# ognite.net
KiCad netlist of a schematic drawn in EAGLE
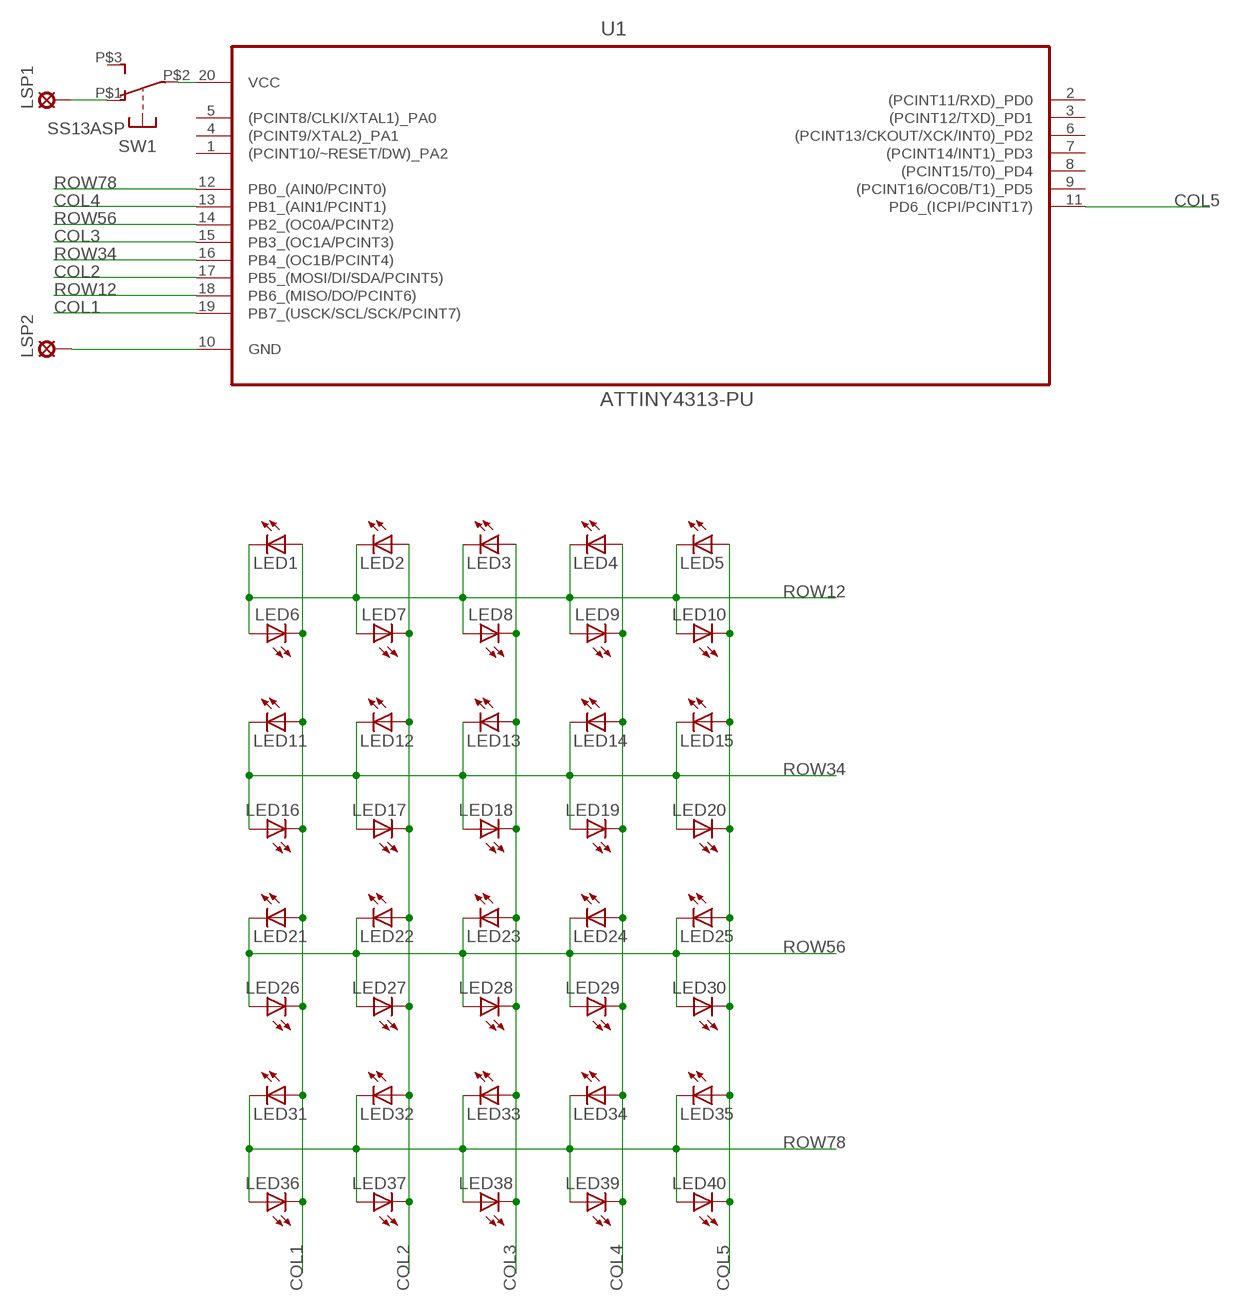
[diagram p0: schematic, sheet 1]

(export (version "E")
  (design (tool "Eeschema 10.0.6"))
  (components
    (comp (ref "LED1")
      (value "LED3MM")
      (footprint "eagle-import:LED3MM")
      (libsource (lib "eagle-import") (part "LED3MM"))
    )
    (comp (ref "LED2")
      (value "LED3MM")
      (footprint "eagle-import:LED3MM")
      (libsource (lib "eagle-import") (part "LED3MM"))
    )
    (comp (ref "LED3")
      (value "LED3MM")
      (footprint "eagle-import:LED3MM")
      (libsource (lib "eagle-import") (part "LED3MM"))
    )
    (comp (ref "LED4")
      (value "LED3MM")
      (footprint "eagle-import:LED3MM")
      (libsource (lib "eagle-import") (part "LED3MM"))
    )
    (comp (ref "LED5")
      (value "LED3MM")
      (footprint "eagle-import:LED3MM")
      (libsource (lib "eagle-import") (part "LED3MM"))
    )
    (comp (ref "LED6")
      (value "LED3MM")
      (footprint "eagle-import:LED3MM")
      (libsource (lib "eagle-import") (part "LED3MM"))
    )
    (comp (ref "LED7")
      (value "LED3MM")
      (footprint "eagle-import:LED3MM")
      (libsource (lib "eagle-import") (part "LED3MM"))
    )
    (comp (ref "LED8")
      (value "LED3MM")
      (footprint "eagle-import:LED3MM")
      (libsource (lib "eagle-import") (part "LED3MM"))
    )
    (comp (ref "LED9")
      (value "LED3MM")
      (footprint "eagle-import:LED3MM")
      (libsource (lib "eagle-import") (part "LED3MM"))
    )
    (comp (ref "LED10")
      (value "LED3MM")
      (footprint "eagle-import:LED3MM")
      (libsource (lib "eagle-import") (part "LED3MM"))
    )
    (comp (ref "LED11")
      (value "LED3MM")
      (footprint "eagle-import:LED3MM")
      (libsource (lib "eagle-import") (part "LED3MM"))
    )
    (comp (ref "LED12")
      (value "LED3MM")
      (footprint "eagle-import:LED3MM")
      (libsource (lib "eagle-import") (part "LED3MM"))
    )
    (comp (ref "LED13")
      (value "LED3MM")
      (footprint "eagle-import:LED3MM")
      (libsource (lib "eagle-import") (part "LED3MM"))
    )
    (comp (ref "LED14")
      (value "LED3MM")
      (footprint "eagle-import:LED3MM")
      (libsource (lib "eagle-import") (part "LED3MM"))
    )
    (comp (ref "LED15")
      (value "LED3MM")
      (footprint "eagle-import:LED3MM")
      (libsource (lib "eagle-import") (part "LED3MM"))
    )
    (comp (ref "LED16")
      (value "LED3MM")
      (footprint "eagle-import:LED3MM")
      (libsource (lib "eagle-import") (part "LED3MM"))
    )
    (comp (ref "LED17")
      (value "LED3MM")
      (footprint "eagle-import:LED3MM")
      (libsource (lib "eagle-import") (part "LED3MM"))
    )
    (comp (ref "LED18")
      (value "LED3MM")
      (footprint "eagle-import:LED3MM")
      (libsource (lib "eagle-import") (part "LED3MM"))
    )
    (comp (ref "LED19")
      (value "LED3MM")
      (footprint "eagle-import:LED3MM")
      (libsource (lib "eagle-import") (part "LED3MM"))
    )
    (comp (ref "LED20")
      (value "LED3MM")
      (footprint "eagle-import:LED3MM")
      (libsource (lib "eagle-import") (part "LED3MM"))
    )
    (comp (ref "LED21")
      (value "LED3MM")
      (footprint "eagle-import:LED3MM")
      (libsource (lib "eagle-import") (part "LED3MM"))
    )
    (comp (ref "LED22")
      (value "LED3MM")
      (footprint "eagle-import:LED3MM")
      (libsource (lib "eagle-import") (part "LED3MM"))
    )
    (comp (ref "LED23")
      (value "LED3MM")
      (footprint "eagle-import:LED3MM")
      (libsource (lib "eagle-import") (part "LED3MM"))
    )
    (comp (ref "LED24")
      (value "LED3MM")
      (footprint "eagle-import:LED3MM")
      (libsource (lib "eagle-import") (part "LED3MM"))
    )
    (comp (ref "LED25")
      (value "LED3MM")
      (footprint "eagle-import:LED3MM")
      (libsource (lib "eagle-import") (part "LED3MM"))
    )
    (comp (ref "LED26")
      (value "LED3MM")
      (footprint "eagle-import:LED3MM")
      (libsource (lib "eagle-import") (part "LED3MM"))
    )
    (comp (ref "LED27")
      (value "LED3MM")
      (footprint "eagle-import:LED3MM")
      (libsource (lib "eagle-import") (part "LED3MM"))
    )
    (comp (ref "LED28")
      (value "LED3MM")
      (footprint "eagle-import:LED3MM")
      (libsource (lib "eagle-import") (part "LED3MM"))
    )
    (comp (ref "LED29")
      (value "LED3MM")
      (footprint "eagle-import:LED3MM")
      (libsource (lib "eagle-import") (part "LED3MM"))
    )
    (comp (ref "LED30")
      (value "LED3MM")
      (footprint "eagle-import:LED3MM")
      (libsource (lib "eagle-import") (part "LED3MM"))
    )
    (comp (ref "LED31")
      (value "LED3MM")
      (footprint "eagle-import:LED3MM")
      (libsource (lib "eagle-import") (part "LED3MM"))
    )
    (comp (ref "LED32")
      (value "LED3MM")
      (footprint "eagle-import:LED3MM")
      (libsource (lib "eagle-import") (part "LED3MM"))
    )
    (comp (ref "LED33")
      (value "LED3MM")
      (footprint "eagle-import:LED3MM")
      (libsource (lib "eagle-import") (part "LED3MM"))
    )
    (comp (ref "LED34")
      (value "LED3MM")
      (footprint "eagle-import:LED3MM")
      (libsource (lib "eagle-import") (part "LED3MM"))
    )
    (comp (ref "LED35")
      (value "LED3MM")
      (footprint "eagle-import:LED3MM")
      (libsource (lib "eagle-import") (part "LED3MM"))
    )
    (comp (ref "LED36")
      (value "LED3MM")
      (footprint "eagle-import:LED3MM")
      (libsource (lib "eagle-import") (part "LED3MM"))
    )
    (comp (ref "LED37")
      (value "LED3MM")
      (footprint "eagle-import:LED3MM")
      (libsource (lib "eagle-import") (part "LED3MM"))
    )
    (comp (ref "LED38")
      (value "LED3MM")
      (footprint "eagle-import:LED3MM")
      (libsource (lib "eagle-import") (part "LED3MM"))
    )
    (comp (ref "LED39")
      (value "LED3MM")
      (footprint "eagle-import:LED3MM")
      (libsource (lib "eagle-import") (part "LED3MM"))
    )
    (comp (ref "LED40")
      (value "LED3MM")
      (footprint "eagle-import:LED3MM")
      (libsource (lib "eagle-import") (part "LED3MM"))
    )
    (comp (ref "LSP1")
      (value "SE14")
      (footprint "eagle-import:SE14")
      (libsource (lib "eagle-import") (part "SE14"))
    )
    (comp (ref "LSP2")
      (value "SE14")
      (footprint "eagle-import:SE14")
      (libsource (lib "eagle-import") (part "SE14"))
    )
    (comp (ref "SW1")
      (value "SS13ASP")
      (footprint "eagle-import:T80-S")
      (libsource (lib "eagle-import") (part "SS13ASP"))
    )
    (comp (ref "U1")
      (value "ATTINY4313-PU")
      (footprint "eagle-import:DIP254P762X533-20")
      (libsource (lib "eagle-import") (part "ATTINY4313-PU"))
    )
  )
  (nets
    (net (code "1") (name "/COL1") (class "Default")
      (node (ref "LED1") (pin "A") (pinfunction "A_A") (pintype "passive"))
      (node (ref "LED11") (pin "A") (pinfunction "A_A") (pintype "passive"))
      (node (ref "LED16") (pin "K") (pinfunction "C_K") (pintype "passive"))
      (node (ref "LED21") (pin "A") (pinfunction "A_A") (pintype "passive"))
      (node (ref "LED26") (pin "K") (pinfunction "C_K") (pintype "passive"))
      (node (ref "LED31") (pin "A") (pinfunction "A_A") (pintype "passive"))
      (node (ref "LED36") (pin "K") (pinfunction "C_K") (pintype "passive"))
      (node (ref "LED6") (pin "K") (pinfunction "C_K") (pintype "passive"))
      (node (ref "U1") (pin "19") (pinfunction "PB7_(USCK/SCL/SCK/PCINT7)_19") (pintype "bidirectional"))
    )
    (net (code "2") (name "/COL2") (class "Default")
      (node (ref "LED12") (pin "A") (pinfunction "A_A") (pintype "passive"))
      (node (ref "LED17") (pin "K") (pinfunction "C_K") (pintype "passive"))
      (node (ref "LED2") (pin "A") (pinfunction "A_A") (pintype "passive"))
      (node (ref "LED22") (pin "A") (pinfunction "A_A") (pintype "passive"))
      (node (ref "LED27") (pin "K") (pinfunction "C_K") (pintype "passive"))
      (node (ref "LED32") (pin "A") (pinfunction "A_A") (pintype "passive"))
      (node (ref "LED37") (pin "K") (pinfunction "C_K") (pintype "passive"))
      (node (ref "LED7") (pin "K") (pinfunction "C_K") (pintype "passive"))
      (node (ref "U1") (pin "17") (pinfunction "PB5_(MOSI/DI/SDA/PCINT5)_17") (pintype "bidirectional"))
    )
    (net (code "3") (name "/COL3") (class "Default")
      (node (ref "LED13") (pin "A") (pinfunction "A_A") (pintype "passive"))
      (node (ref "LED18") (pin "K") (pinfunction "C_K") (pintype "passive"))
      (node (ref "LED23") (pin "A") (pinfunction "A_A") (pintype "passive"))
      (node (ref "LED28") (pin "K") (pinfunction "C_K") (pintype "passive"))
      (node (ref "LED3") (pin "A") (pinfunction "A_A") (pintype "passive"))
      (node (ref "LED33") (pin "A") (pinfunction "A_A") (pintype "passive"))
      (node (ref "LED38") (pin "K") (pinfunction "C_K") (pintype "passive"))
      (node (ref "LED8") (pin "K") (pinfunction "C_K") (pintype "passive"))
      (node (ref "U1") (pin "15") (pinfunction "PB3_(OC1A/PCINT3)_15") (pintype "power_in"))
    )
    (net (code "4") (name "/COL4") (class "Default")
      (node (ref "LED14") (pin "A") (pinfunction "A_A") (pintype "passive"))
      (node (ref "LED19") (pin "K") (pinfunction "C_K") (pintype "passive"))
      (node (ref "LED24") (pin "A") (pinfunction "A_A") (pintype "passive"))
      (node (ref "LED29") (pin "K") (pinfunction "C_K") (pintype "passive"))
      (node (ref "LED34") (pin "A") (pinfunction "A_A") (pintype "passive"))
      (node (ref "LED39") (pin "K") (pinfunction "C_K") (pintype "passive"))
      (node (ref "LED4") (pin "A") (pinfunction "A_A") (pintype "passive"))
      (node (ref "LED9") (pin "K") (pinfunction "C_K") (pintype "passive"))
      (node (ref "U1") (pin "13") (pinfunction "PB1_(AIN1/PCINT1)_13") (pintype "bidirectional"))
    )
    (net (code "5") (name "/COL5") (class "Default")
      (node (ref "LED10") (pin "K") (pinfunction "C_K") (pintype "passive"))
      (node (ref "LED15") (pin "A") (pinfunction "A_A") (pintype "passive"))
      (node (ref "LED20") (pin "K") (pinfunction "C_K") (pintype "passive"))
      (node (ref "LED25") (pin "A") (pinfunction "A_A") (pintype "passive"))
      (node (ref "LED30") (pin "K") (pinfunction "C_K") (pintype "passive"))
      (node (ref "LED35") (pin "A") (pinfunction "A_A") (pintype "passive"))
      (node (ref "LED40") (pin "K") (pinfunction "C_K") (pintype "passive"))
      (node (ref "LED5") (pin "A") (pinfunction "A_A") (pintype "passive"))
      (node (ref "U1") (pin "11") (pinfunction "PD6_(ICPI/PCINT17)_11") (pintype "bidirectional"))
    )
    (net (code "6") (name "/ROW12") (class "Default")
      (node (ref "LED1") (pin "K") (pinfunction "C_K") (pintype "passive"))
      (node (ref "LED10") (pin "A") (pinfunction "A_A") (pintype "passive"))
      (node (ref "LED2") (pin "K") (pinfunction "C_K") (pintype "passive"))
      (node (ref "LED3") (pin "K") (pinfunction "C_K") (pintype "passive"))
      (node (ref "LED4") (pin "K") (pinfunction "C_K") (pintype "passive"))
      (node (ref "LED5") (pin "K") (pinfunction "C_K") (pintype "passive"))
      (node (ref "LED6") (pin "A") (pinfunction "A_A") (pintype "passive"))
      (node (ref "LED7") (pin "A") (pinfunction "A_A") (pintype "passive"))
      (node (ref "LED8") (pin "A") (pinfunction "A_A") (pintype "passive"))
      (node (ref "LED9") (pin "A") (pinfunction "A_A") (pintype "passive"))
      (node (ref "U1") (pin "18") (pinfunction "PB6_(MISO/DO/PCINT6)_18") (pintype "bidirectional"))
    )
    (net (code "7") (name "/ROW34") (class "Default")
      (node (ref "LED11") (pin "K") (pinfunction "C_K") (pintype "passive"))
      (node (ref "LED12") (pin "K") (pinfunction "C_K") (pintype "passive"))
      (node (ref "LED13") (pin "K") (pinfunction "C_K") (pintype "passive"))
      (node (ref "LED14") (pin "K") (pinfunction "C_K") (pintype "passive"))
      (node (ref "LED15") (pin "K") (pinfunction "C_K") (pintype "passive"))
      (node (ref "LED16") (pin "A") (pinfunction "A_A") (pintype "passive"))
      (node (ref "LED17") (pin "A") (pinfunction "A_A") (pintype "passive"))
      (node (ref "LED18") (pin "A") (pinfunction "A_A") (pintype "passive"))
      (node (ref "LED19") (pin "A") (pinfunction "A_A") (pintype "passive"))
      (node (ref "LED20") (pin "A") (pinfunction "A_A") (pintype "passive"))
      (node (ref "U1") (pin "16") (pinfunction "PB4_(OC1B/PCINT4)_16") (pintype "passive"))
    )
    (net (code "8") (name "/ROW56") (class "Default")
      (node (ref "LED21") (pin "K") (pinfunction "C_K") (pintype "passive"))
      (node (ref "LED22") (pin "K") (pinfunction "C_K") (pintype "passive"))
      (node (ref "LED23") (pin "K") (pinfunction "C_K") (pintype "passive"))
      (node (ref "LED24") (pin "K") (pinfunction "C_K") (pintype "passive"))
      (node (ref "LED25") (pin "K") (pinfunction "C_K") (pintype "passive"))
      (node (ref "LED26") (pin "A") (pinfunction "A_A") (pintype "passive"))
      (node (ref "LED27") (pin "A") (pinfunction "A_A") (pintype "passive"))
      (node (ref "LED28") (pin "A") (pinfunction "A_A") (pintype "passive"))
      (node (ref "LED29") (pin "A") (pinfunction "A_A") (pintype "passive"))
      (node (ref "LED30") (pin "A") (pinfunction "A_A") (pintype "passive"))
      (node (ref "U1") (pin "14") (pinfunction "PB2_(OC0A/PCINT2)_14") (pintype "bidirectional"))
    )
    (net (code "9") (name "/ROW78") (class "Default")
      (node (ref "LED31") (pin "K") (pinfunction "C_K") (pintype "passive"))
      (node (ref "LED32") (pin "K") (pinfunction "C_K") (pintype "passive"))
      (node (ref "LED33") (pin "K") (pinfunction "C_K") (pintype "passive"))
      (node (ref "LED34") (pin "K") (pinfunction "C_K") (pintype "passive"))
      (node (ref "LED35") (pin "K") (pinfunction "C_K") (pintype "passive"))
      (node (ref "LED36") (pin "A") (pinfunction "A_A") (pintype "passive"))
      (node (ref "LED37") (pin "A") (pinfunction "A_A") (pintype "passive"))
      (node (ref "LED38") (pin "A") (pinfunction "A_A") (pintype "passive"))
      (node (ref "LED39") (pin "A") (pinfunction "A_A") (pintype "passive"))
      (node (ref "LED40") (pin "A") (pinfunction "A_A") (pintype "passive"))
      (node (ref "U1") (pin "12") (pinfunction "PB0_(AIN0/PCINT0)_12") (pintype "bidirectional"))
    )
    (net (code "10") (name "Net-(SW1-COM)") (class "Default")
      (node (ref "SW1") (pin "P$2") (pinfunction "COM_P$2") (pintype "passive"))
      (node (ref "U1") (pin "20") (pinfunction "VCC_20") (pintype "power_in"))
    )
    (net (code "11") (name "Net-(SW1-S1)") (class "Default")
      (node (ref "LSP1") (pin "MP") (pinfunction "MP_MP") (pintype "passive"))
      (node (ref "SW1") (pin "P$1") (pinfunction "S1_P$1") (pintype "passive"))
    )
    (net (code "12") (name "Net-(U1-GND)") (class "Default")
      (node (ref "LSP2") (pin "MP") (pinfunction "MP_MP") (pintype "passive"))
      (node (ref "U1") (pin "10") (pinfunction "GND_10") (pintype "passive"))
    )
    (net (code "13") (name "unconnected-(SW1-S2-PadP$3)") (class "Default")
      (node (ref "SW1") (pin "P$3") (pinfunction "S2_P$3") (pintype "passive"))
    )
    (net (code "14") (name "unconnected-(U1-(PCINT8{slash}CLKI{slash}XTAL1)_PA0-Pad5)") (class "Default")
      (node (ref "U1") (pin "5") (pinfunction "(PCINT8/CLKI/XTAL1)_PA0_5") (pintype "bidirectional"))
    )
    (net (code "15") (name "unconnected-(U1-(PCINT9{slash}XTAL2)_PA1-Pad4)") (class "Default")
      (node (ref "U1") (pin "4") (pinfunction "(PCINT9/XTAL2)_PA1_4") (pintype "bidirectional"))
    )
    (net (code "16") (name "unconnected-(U1-(PCINT10{slash}~{RESET{slash}DW})_PA2-Pad1)") (class "Default")
      (node (ref "U1") (pin "1") (pinfunction "(PCINT10/~{RESET/DW})_PA2_1") (pintype "bidirectional"))
    )
    (net (code "17") (name "unconnected-(U1-(PCINT11{slash}RXD)_PD0-Pad2)") (class "Default")
      (node (ref "U1") (pin "2") (pinfunction "(PCINT11/RXD)_PD0_2") (pintype "bidirectional"))
    )
    (net (code "18") (name "unconnected-(U1-(PCINT12{slash}TXD)_PD1-Pad3)") (class "Default")
      (node (ref "U1") (pin "3") (pinfunction "(PCINT12/TXD)_PD1_3") (pintype "bidirectional"))
    )
    (net (code "19") (name "unconnected-(U1-(PCINT13{slash}CKOUT{slash}XCK{slash}INT0)_PD2-Pad6)") (class "Default")
      (node (ref "U1") (pin "6") (pinfunction "(PCINT13/CKOUT/XCK/INT0)_PD2_6") (pintype "bidirectional"))
    )
    (net (code "20") (name "unconnected-(U1-(PCINT14{slash}INT1)_PD3-Pad7)") (class "Default")
      (node (ref "U1") (pin "7") (pinfunction "(PCINT14/INT1)_PD3_7") (pintype "bidirectional"))
    )
    (net (code "21") (name "unconnected-(U1-(PCINT15{slash}T0)_PD4-Pad8)") (class "Default")
      (node (ref "U1") (pin "8") (pinfunction "(PCINT15/T0)_PD4_8") (pintype "bidirectional"))
    )
    (net (code "22") (name "unconnected-(U1-(PCINT16{slash}OC0B{slash}T1)_PD5-Pad9)") (class "Default")
      (node (ref "U1") (pin "9") (pinfunction "(PCINT16/OC0B/T1)_PD5_9") (pintype "bidirectional"))
    )
  )
)
